# Seeeduino_XIAO_Expansion_board_v1_0_2008.net
KiCad netlist of a schematic drawn in EAGLE
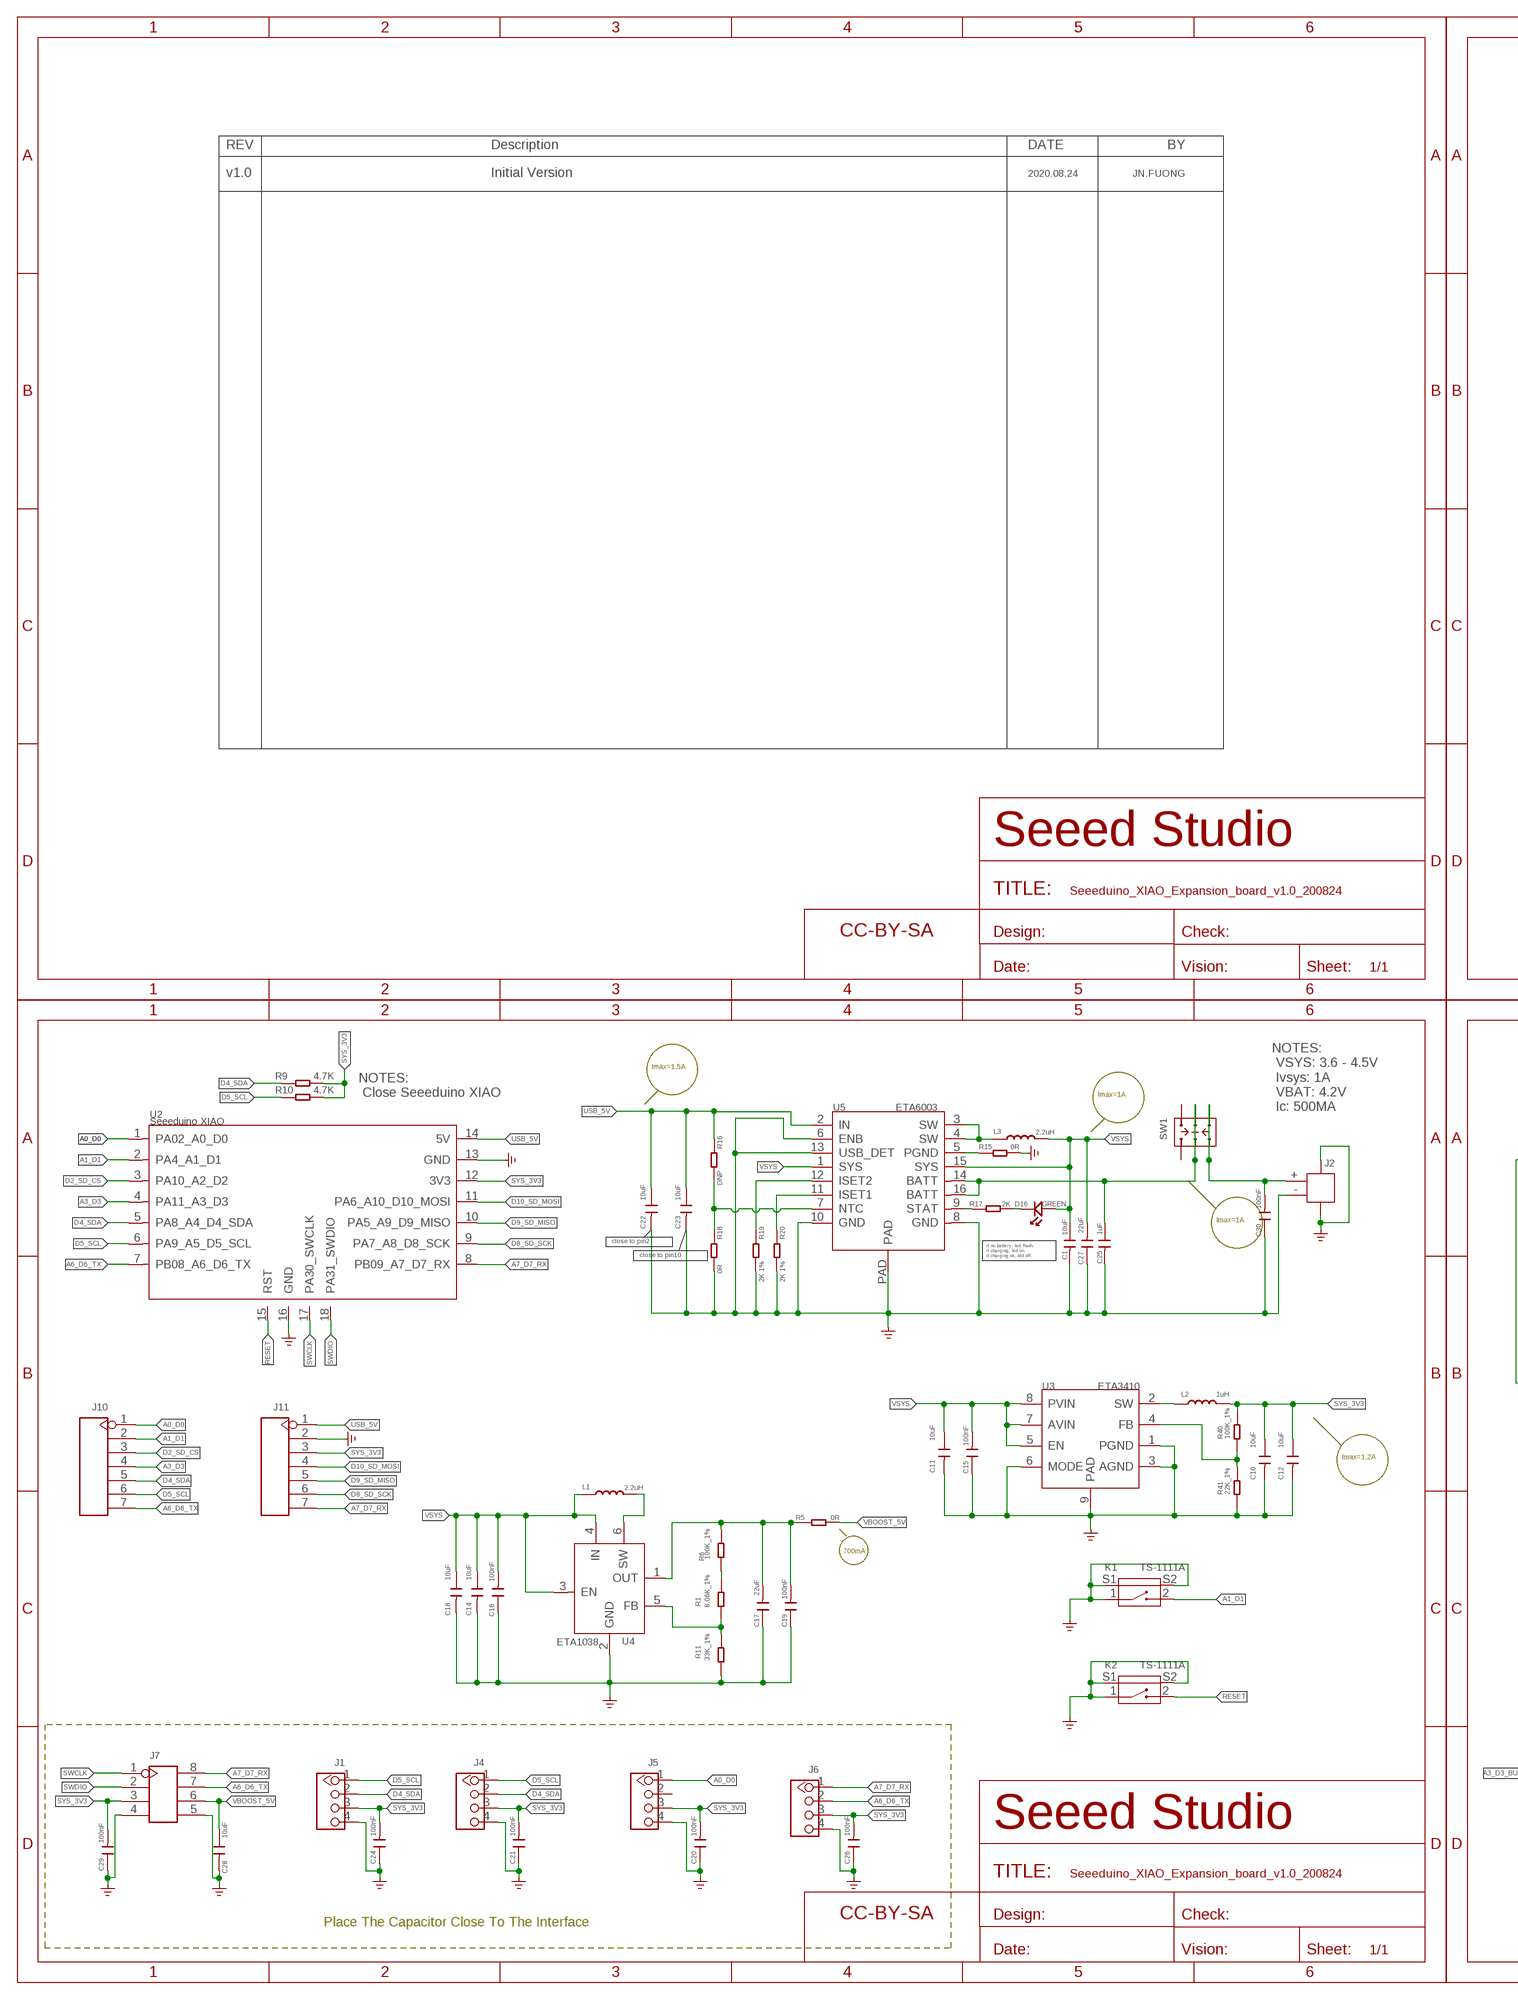
[diagram p0: schematic, sheet 1, part 1 of 2]
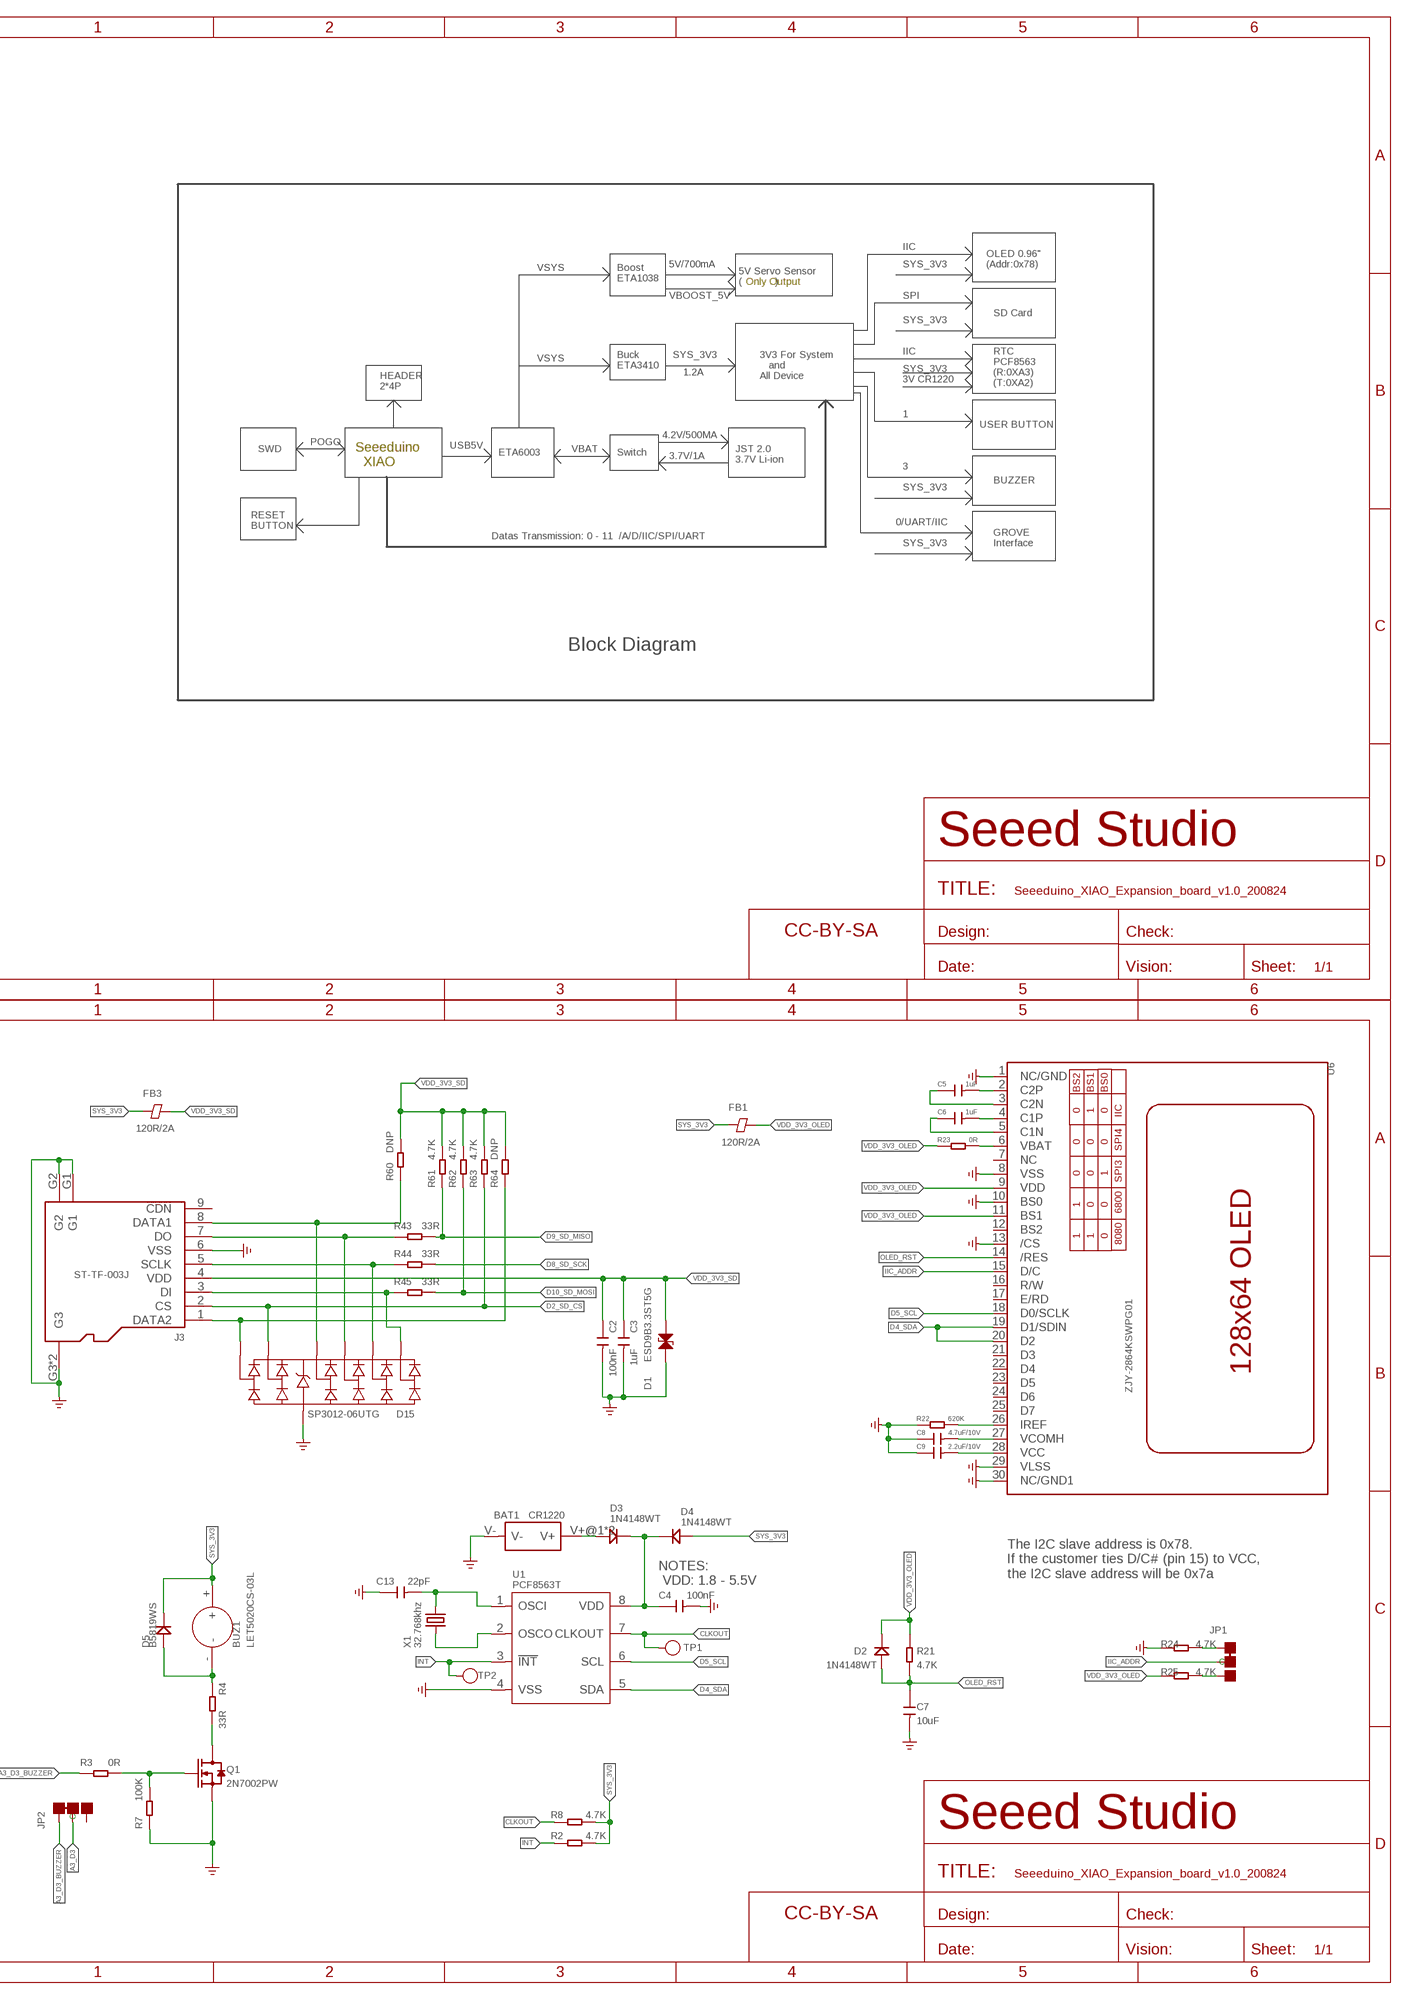
[diagram p1: schematic, sheet 1, part 2 of 2]

(export (version "E")
  (design (tool "Eeschema 10.0.6"))
  (components
    (comp (ref "BAT1")
      (value "CR1220")
      (footprint "eagle-import:BAT2P-SMD-13.2X12.1X3.2MM")
      (libsource (lib "eagle-import") (part "BAT-HOLDER-KST-1206"))
    )
    (comp (ref "BUZ1")
      (value "LET5020CS-03L")
      (footprint "eagle-import:BZ3-SMD-5.0X5.0X2.5MM")
      (libsource (lib "eagle-import") (part "BUZZER-312020004"))
    )
    (comp (ref "C1")
      (value "10uF")
      (footprint "eagle-import:C0603")
      (libsource (lib "eagle-import") (part "C-0603"))
    )
    (comp (ref "C2")
      (value "100nF")
      (footprint "eagle-import:C0402")
      (libsource (lib "eagle-import") (part "C-0402"))
    )
    (comp (ref "C3")
      (value "1uF")
      (footprint "eagle-import:C0402")
      (libsource (lib "eagle-import") (part "C-0402"))
    )
    (comp (ref "C4")
      (value "100nF")
      (footprint "eagle-import:C0402")
      (libsource (lib "eagle-import") (part "C-0402"))
    )
    (comp (ref "C5")
      (value "1uF")
      (footprint "eagle-import:C0402")
      (libsource (lib "eagle-import") (part "C-0402"))
    )
    (comp (ref "C6")
      (value "1uF")
      (footprint "eagle-import:C0402")
      (libsource (lib "eagle-import") (part "C-0402"))
    )
    (comp (ref "C7")
      (value "10uF")
      (footprint "eagle-import:C0603")
      (libsource (lib "eagle-import") (part "C-0603"))
    )
    (comp (ref "C8")
      (value "4.7uF/10V")
      (footprint "eagle-import:C0603")
      (libsource (lib "eagle-import") (part "C-0603"))
    )
    (comp (ref "C9")
      (value "2.2uF/10V")
      (footprint "eagle-import:C0603")
      (libsource (lib "eagle-import") (part "C-0603"))
    )
    (comp (ref "C10")
      (value "10uF")
      (footprint "eagle-import:C0603")
      (libsource (lib "eagle-import") (part "C-0603"))
    )
    (comp (ref "C11")
      (value "10uF")
      (footprint "eagle-import:C0603")
      (libsource (lib "eagle-import") (part "C-0603"))
    )
    (comp (ref "C12")
      (value "10uF")
      (footprint "eagle-import:C0603")
      (libsource (lib "eagle-import") (part "C-0603"))
    )
    (comp (ref "C13")
      (value "22pF")
      (footprint "eagle-import:C0402")
      (libsource (lib "eagle-import") (part "C-0402"))
    )
    (comp (ref "C14")
      (value "10uF")
      (footprint "eagle-import:C0603")
      (libsource (lib "eagle-import") (part "C-0603"))
    )
    (comp (ref "C15")
      (value "100nF")
      (footprint "eagle-import:C0402")
      (libsource (lib "eagle-import") (part "C-0402"))
    )
    (comp (ref "C16")
      (value "100nF")
      (footprint "eagle-import:C0402")
      (libsource (lib "eagle-import") (part "C-0402"))
    )
    (comp (ref "C17")
      (value "22uF")
      (footprint "eagle-import:C0603")
      (libsource (lib "eagle-import") (part "C-0603"))
    )
    (comp (ref "C18")
      (value "10uF")
      (footprint "eagle-import:C0603")
      (libsource (lib "eagle-import") (part "C-0603"))
    )
    (comp (ref "C19")
      (value "100nF")
      (footprint "eagle-import:C0402")
      (libsource (lib "eagle-import") (part "C-0402"))
    )
    (comp (ref "C20")
      (value "100nF")
      (footprint "eagle-import:C0402")
      (libsource (lib "eagle-import") (part "C-0402"))
    )
    (comp (ref "C21")
      (value "100nF")
      (footprint "eagle-import:C0402")
      (libsource (lib "eagle-import") (part "C-0402"))
    )
    (comp (ref "C22")
      (value "10uF")
      (footprint "eagle-import:C0603")
      (libsource (lib "eagle-import") (part "C-0603"))
    )
    (comp (ref "C23")
      (value "10uF")
      (footprint "eagle-import:C0603")
      (libsource (lib "eagle-import") (part "C-0603"))
    )
    (comp (ref "C24")
      (value "100nF")
      (footprint "eagle-import:C0402")
      (libsource (lib "eagle-import") (part "C-0402"))
    )
    (comp (ref "C25")
      (value "1uF")
      (footprint "eagle-import:C0402")
      (libsource (lib "eagle-import") (part "C-0402"))
    )
    (comp (ref "C26")
      (value "100nF")
      (footprint "eagle-import:C0402")
      (libsource (lib "eagle-import") (part "C-0402"))
    )
    (comp (ref "C27")
      (value "22uF")
      (footprint "eagle-import:C0603")
      (libsource (lib "eagle-import") (part "C-0603"))
    )
    (comp (ref "C28")
      (value "10uF")
      (footprint "eagle-import:C0603")
      (libsource (lib "eagle-import") (part "C-0603"))
    )
    (comp (ref "C29")
      (value "100nF")
      (footprint "eagle-import:C0402")
      (libsource (lib "eagle-import") (part "C-0402"))
    )
    (comp (ref "C30")
      (value "100nF")
      (footprint "eagle-import:C0603")
      (libsource (lib "eagle-import") (part "C-0603"))
    )
    (comp (ref "D1")
      (value "ESD9B3.3ST5G")
      (footprint "eagle-import:ESD-0402")
      (libsource (lib "eagle-import") (part "D-ESD-2P-DOUBLE-0402"))
    )
    (comp (ref "D2")
      (value "1N4148WT")
      (footprint "eagle-import:SOD-523")
      (libsource (lib "eagle-import") (part "DIODE'0603'"))
    )
    (comp (ref "D3")
      (value "1N4148WT")
      (footprint "eagle-import:SOD-523")
      (libsource (lib "eagle-import") (part "DIODE'0603'"))
    )
    (comp (ref "D4")
      (value "1N4148WT")
      (footprint "eagle-import:SOD-523")
      (libsource (lib "eagle-import") (part "DIODE'0603'"))
    )
    (comp (ref "D5")
      (value "B5819WS")
      (footprint "eagle-import:SOD-323")
      (libsource (lib "eagle-import") (part "DIODE'0805'"))
    )
    (comp (ref "D15")
      (value "SP3012-06UTG")
      (footprint "eagle-import:UDFN14-0.5-3.5X1.35X0.5MM")
      (libsource (lib "eagle-import") (part "D-ESD-14P"))
    )
    (comp (ref "D16")
      (value "GREEN")
      (footprint "eagle-import:LED-0402")
      (libsource (lib "eagle-import") (part "LED-0402"))
    )
    (comp (ref "FB1")
      (value "120R/2A")
      (footprint "eagle-import:F0402")
      (libsource (lib "eagle-import") (part "FERRITE-BEAD-0402"))
    )
    (comp (ref "FB3")
      (value "120R/2A")
      (footprint "eagle-import:F0402")
      (libsource (lib "eagle-import") (part "FERRITE-BEAD-0402"))
    )
    (comp (ref "FR1")
      (value "SEEEDSTUDIO-OPEN-SCH-FRAME")
      (footprint "eagle-import:SEEEDSTUDIO-PCB-FRAME")
      (libsource (lib "eagle-import") (part "SEEEDSTUDIO-OPEN-SCH-FRAME"))
    )
    (comp (ref "FR2")
      (value "SEEEDSTUDIO-OPEN-SCH-FRAME")
      (footprint "eagle-import:SEEEDSTUDIO-PCB-FRAME")
      (libsource (lib "eagle-import") (part "SEEEDSTUDIO-OPEN-SCH-FRAME"))
    )
    (comp (ref "FR3")
      (value "SEEEDSTUDIO-OPEN-SCH-FRAME")
      (footprint "eagle-import:SEEEDSTUDIO-PCB-FRAME")
      (libsource (lib "eagle-import") (part "SEEEDSTUDIO-OPEN-SCH-FRAME"))
    )
    (comp (ref "FR5")
      (value "SEEEDSTUDIO-OPEN-SCH-FRAME")
      (footprint "eagle-import:SEEEDSTUDIO-PCB-FRAME")
      (libsource (lib "eagle-import") (part "SEEEDSTUDIO-OPEN-SCH-FRAME"))
    )
    (comp (ref "J1")
      (value "GROVE-CONNECTOR-DIP-320110034")
      (footprint "eagle-import:HW4-2.0-90D")
      (libsource (lib "eagle-import") (part "GROVE-CONNECTOR-DIP-320110034"))
    )
    (comp (ref "J2")
      (value "JST-2P-SMD'2.0'")
      (footprint "eagle-import:HW2-SMD-2.0-90D")
      (libsource (lib "eagle-import") (part "JST-2P-SMD'2.0'"))
    )
    (comp (ref "J3")
      (value "ST-TF-003J")
      (footprint "eagle-import:MICRO-SD9+4P-SMD-16.1X14.5X1.85MM")
      (libsource (lib "eagle-import") (part "MICRO-SD-CARD-HOLDER-9P-320090000"))
    )
    (comp (ref "J4")
      (value "GROVE-CONNECTOR-DIP-320110034")
      (footprint "eagle-import:HW4-2.0-90D")
      (libsource (lib "eagle-import") (part "GROVE-CONNECTOR-DIP-320110034"))
    )
    (comp (ref "J5")
      (value "GROVE-CONNECTOR-DIP-320110034")
      (footprint "eagle-import:HW4-2.0-90D")
      (libsource (lib "eagle-import") (part "GROVE-CONNECTOR-DIP-320110034"))
    )
    (comp (ref "J6")
      (value "GROVE-CONNECTOR-DIP-320110034")
      (footprint "eagle-import:HW4-2.0-90D")
      (libsource (lib "eagle-import") (part "GROVE-CONNECTOR-DIP-320110034"))
    )
    (comp (ref "J7")
      (value "HEADER-2X4P-2.54-SMD")
      (footprint "eagle-import:H2X4-SMD-2.54")
      (libsource (lib "eagle-import") (part "HEADER-2X4P-2.54-SMD"))
    )
    (comp (ref "J10")
      (value "HEADER-7P-2.54")
      (footprint "eagle-import:H7-2.54")
      (libsource (lib "eagle-import") (part "HEADER-7P-2.54"))
    )
    (comp (ref "J11")
      (value "HEADER-7P-2.54")
      (footprint "eagle-import:H7-2.54")
      (libsource (lib "eagle-import") (part "HEADER-7P-2.54"))
    )
    (comp (ref "JP1")
      (value "JP-3P-SHORT")
      (footprint "eagle-import:3P-SMD-SHORT")
      (libsource (lib "eagle-import") (part "JP-3P-SHORT"))
    )
    (comp (ref "JP2")
      (value "JP-3P-SHORT")
      (footprint "eagle-import:3P-SMD-SHORT")
      (libsource (lib "eagle-import") (part "JP-3P-SHORT"))
    )
    (comp (ref "K1")
      (value "TS-1111A")
      (footprint "eagle-import:SW4-SMD-4.5X3.8X1.8MM-90D")
      (libsource (lib "eagle-import") (part "BUTTON-2+2P'HQ-TP-1100A'"))
    )
    (comp (ref "K2")
      (value "TS-1111A")
      (footprint "eagle-import:SW4-SMD-4.5X3.8X1.8MM-90D")
      (libsource (lib "eagle-import") (part "BUTTON-2+2P'HQ-TP-1100A'"))
    )
    (comp (ref "L1")
      (value "2.2uH")
      (footprint "eagle-import:L0806")
      (libsource (lib "eagle-import") (part "INDUCTOR/FERRITE-BEAD'0806'"))
    )
    (comp (ref "L2")
      (value "1uH")
      (footprint "eagle-import:L201610")
      (libsource (lib "eagle-import") (part "L-MPM201610SR33_T"))
    )
    (comp (ref "L3")
      (value "2.2uH")
      (footprint "eagle-import:L0806")
      (libsource (lib "eagle-import") (part "INDUCTOR/FERRITE-BEAD'0806'"))
    )
    (comp (ref "Q1")
      (value "2N7002PW")
      (footprint "eagle-import:SOT-323")
      (libsource (lib "eagle-import") (part "MOSFET-N-SI1304BDL"))
    )
    (comp (ref "R1")
      (value "8.06K_1%")
      (footprint "eagle-import:R0402")
      (libsource (lib "eagle-import") (part "R-0402"))
    )
    (comp (ref "R2")
      (value "4.7K")
      (footprint "eagle-import:R0402")
      (libsource (lib "eagle-import") (part "R-0402"))
    )
    (comp (ref "R3")
      (value "0R")
      (footprint "eagle-import:R0402")
      (libsource (lib "eagle-import") (part "R-0402"))
    )
    (comp (ref "R4")
      (value "33R")
      (footprint "eagle-import:R0402")
      (libsource (lib "eagle-import") (part "R-0402"))
    )
    (comp (ref "R5")
      (value "0R")
      (footprint "eagle-import:R0603")
      (libsource (lib "eagle-import") (part "R-0603"))
    )
    (comp (ref "R6")
      (value "100K_1%")
      (footprint "eagle-import:R0402")
      (libsource (lib "eagle-import") (part "R-0402"))
    )
    (comp (ref "R7")
      (value "100K")
      (footprint "eagle-import:R0402")
      (libsource (lib "eagle-import") (part "R-0402"))
    )
    (comp (ref "R8")
      (value "4.7K")
      (footprint "eagle-import:R0402")
      (libsource (lib "eagle-import") (part "R-0402"))
    )
    (comp (ref "R9")
      (value "4.7K")
      (footprint "eagle-import:R0402")
      (libsource (lib "eagle-import") (part "R-0402"))
    )
    (comp (ref "R10")
      (value "4.7K")
      (footprint "eagle-import:R0402")
      (libsource (lib "eagle-import") (part "R-0402"))
    )
    (comp (ref "R11")
      (value "33K_1%")
      (footprint "eagle-import:R0402")
      (libsource (lib "eagle-import") (part "R-0402"))
    )
    (comp (ref "R15")
      (value "0R")
      (footprint "eagle-import:R0402")
      (libsource (lib "eagle-import") (part "R-0402"))
    )
    (comp (ref "R16")
      (value "DNP")
      (footprint "eagle-import:R0402")
      (libsource (lib "eagle-import") (part "R-0402"))
    )
    (comp (ref "R17")
      (value "2K")
      (footprint "eagle-import:R0402")
      (libsource (lib "eagle-import") (part "R-0402"))
    )
    (comp (ref "R18")
      (value "0R")
      (footprint "eagle-import:R0402")
      (libsource (lib "eagle-import") (part "R-0402"))
    )
    (comp (ref "R19")
      (value "2K 1%")
      (footprint "eagle-import:R0402")
      (libsource (lib "eagle-import") (part "R-0402"))
    )
    (comp (ref "R20")
      (value "2K 1%")
      (footprint "eagle-import:R0402")
      (libsource (lib "eagle-import") (part "R-0402"))
    )
    (comp (ref "R21")
      (value "4.7K")
      (footprint "eagle-import:R0402")
      (libsource (lib "eagle-import") (part "R-0402"))
    )
    (comp (ref "R22")
      (value "620K")
      (footprint "eagle-import:R0402")
      (libsource (lib "eagle-import") (part "R-0402"))
    )
    (comp (ref "R23")
      (value "0R")
      (footprint "eagle-import:R0402")
      (libsource (lib "eagle-import") (part "R-0402"))
    )
    (comp (ref "R24")
      (value "4.7K")
      (footprint "eagle-import:R0402")
      (libsource (lib "eagle-import") (part "R-0402"))
    )
    (comp (ref "R25")
      (value "4.7K")
      (footprint "eagle-import:R0402")
      (libsource (lib "eagle-import") (part "R-0402"))
    )
    (comp (ref "R40")
      (value "100K_1%")
      (footprint "eagle-import:R0402")
      (libsource (lib "eagle-import") (part "R-0402"))
    )
    (comp (ref "R41")
      (value "22K_1%")
      (footprint "eagle-import:R0402")
      (libsource (lib "eagle-import") (part "R-0402"))
    )
    (comp (ref "R43")
      (value "33R")
      (footprint "eagle-import:R0402")
      (libsource (lib "eagle-import") (part "R-0402"))
    )
    (comp (ref "R44")
      (value "33R")
      (footprint "eagle-import:R0402")
      (libsource (lib "eagle-import") (part "R-0402"))
    )
    (comp (ref "R45")
      (value "33R")
      (footprint "eagle-import:R0402")
      (libsource (lib "eagle-import") (part "R-0402"))
    )
    (comp (ref "R60")
      (value "DNP")
      (footprint "eagle-import:R0402")
      (libsource (lib "eagle-import") (part "R-0402"))
    )
    (comp (ref "R61")
      (value "4.7K")
      (footprint "eagle-import:R0402")
      (libsource (lib "eagle-import") (part "R-0402"))
    )
    (comp (ref "R62")
      (value "4.7K")
      (footprint "eagle-import:R0402")
      (libsource (lib "eagle-import") (part "R-0402"))
    )
    (comp (ref "R63")
      (value "4.7K")
      (footprint "eagle-import:R0402")
      (libsource (lib "eagle-import") (part "R-0402"))
    )
    (comp (ref "R64")
      (value "DNP")
      (footprint "eagle-import:R0402")
      (libsource (lib "eagle-import") (part "R-0402"))
    )
    (comp (ref "SW1")
      (value "SWITCH-2CH-6P-311030004")
      (footprint "eagle-import:SW6-2.54-9.0X3.5X3.2MM-90D")
      (libsource (lib "eagle-import") (part "SWITCH-2CH-6P-311030004"))
    )
    (comp (ref "TP1")
      (value "TEST-POINT'4545'")
      (footprint "eagle-import:TP-D45MIL")
      (fields (field (name "PARTNO") "DNP"))
      (libsource (lib "eagle-import") (part "TEST-POINT'4545'"))
    )
    (comp (ref "TP2")
      (value "TEST-POINT'4545'")
      (footprint "eagle-import:TP-D45MIL")
      (fields (field (name "PARTNO") "DNP"))
      (libsource (lib "eagle-import") (part "TEST-POINT'4545'"))
    )
    (comp (ref "U1")
      (value "PCF8563T")
      (footprint "eagle-import:SOP8-1.27-5X3.9MM")
      (libsource (lib "eagle-import") (part "RTC-PCF8563T"))
    )
    (comp (ref "U2")
      (value "Seeeduino XIAO")
      (footprint "eagle-import:MOUDLE14P-2.54-21X17.8MM-TEST")
      (libsource (lib "eagle-import") (part "MOUDLE-SEEEDUINO-XIAO-TEST-DIP"))
    )
    (comp (ref "U3")
      (value "ETA3410")
      (footprint "eagle-import:DFN8G-0.5-2X2MM")
      (libsource (lib "eagle-import") (part "CONVERTER-ETA3410"))
    )
    (comp (ref "U4")
      (value "ETA1038")
      (footprint "eagle-import:SOT-23-6")
      (libsource (lib "eagle-import") (part "CONVERTER-ETA1038"))
    )
    (comp (ref "U5")
      (value "ETA6003")
      (footprint "eagle-import:QFN16GA-0.5-3X3MM")
      (libsource (lib "eagle-import") (part "PMIC-ETA6003-310990023"))
    )
    (comp (ref "U6")
      (value "ZJY-2864KSWPG01")
      (footprint "eagle-import:OLED30P-0.7-24.74X16.9MM")
      (libsource (lib "eagle-import") (part "OLED-12864-30P"))
    )
    (comp (ref "X1")
      (value "32.768khz")
      (footprint "eagle-import:X2-SMD-L2.0X1.2X0.55MM")
      (libsource (lib "eagle-import") (part "CRYSTAL-2P'NX2012SA'"))
    )
  )
  (nets
    (net (code "1") (name "A0_D0") (class "Default")
      (node (ref "J10") (pin "1") (pinfunction "1_1") (pintype "bidirectional"))
      (node (ref "J5") (pin "1") (pinfunction "1_1") (pintype "bidirectional"))
      (node (ref "U2") (pin "1") (pinfunction "PA02_A0_D0_1") (pintype "bidirectional"))
    )
    (net (code "2") (name "A1_D1") (class "Default")
      (node (ref "J10") (pin "2") (pinfunction "2_2") (pintype "bidirectional"))
      (node (ref "K1") (pin "2") (pinfunction "2_2") (pintype "bidirectional"))
      (node (ref "U2") (pin "2") (pinfunction "PA4_A1_D1_2") (pintype "bidirectional"))
    )
    (net (code "3") (name "A3_D3") (class "Default")
      (node (ref "J10") (pin "4") (pinfunction "4_4") (pintype "bidirectional"))
      (node (ref "JP2") (pin "MM") (pinfunction "C_MM") (pintype "bidirectional"))
      (node (ref "U2") (pin "4") (pinfunction "PA11_A3_D3_4") (pintype "bidirectional"))
    )
    (net (code "4") (name "A3_D3_BUZZER") (class "Default")
      (node (ref "JP2") (pin "11") (pinfunction "L_11") (pintype "bidirectional"))
      (node (ref "R3") (pin "1") (pinfunction "1_1") (pintype "passive"))
    )
    (net (code "5") (name "A6_D6_TX") (class "Default")
      (node (ref "J10") (pin "7") (pinfunction "7_7") (pintype "bidirectional"))
      (node (ref "J6") (pin "2") (pinfunction "2_2") (pintype "bidirectional"))
      (node (ref "J7") (pin "7") (pinfunction "7_7") (pintype "bidirectional"))
      (node (ref "U2") (pin "7") (pinfunction "PB08_A6_D6_TX_7") (pintype "bidirectional"))
    )
    (net (code "6") (name "A7_D7_RX") (class "Default")
      (node (ref "J11") (pin "7") (pinfunction "7_7") (pintype "bidirectional"))
      (node (ref "J6") (pin "1") (pinfunction "1_1") (pintype "bidirectional"))
      (node (ref "J7") (pin "8") (pinfunction "8_8") (pintype "bidirectional"))
      (node (ref "U2") (pin "8") (pinfunction "PB09_A7_D7_RX_8") (pintype "bidirectional"))
    )
    (net (code "7") (name "CLKOUT") (class "Default")
      (node (ref "R8") (pin "1") (pinfunction "1_1") (pintype "passive"))
      (node (ref "TP1") (pin "T") (pinfunction "T_T") (pintype "bidirectional"))
      (node (ref "U1") (pin "7") (pinfunction "CLKOUT_7") (pintype "bidirectional"))
    )
    (net (code "8") (name "D2_SD_CS") (class "Default")
      (node (ref "D15") (pin "6") (pinfunction "9_6") (pintype "bidirectional"))
      (node (ref "D15") (pin "9") (pinfunction "9_9") (pintype "bidirectional"))
      (node (ref "J10") (pin "3") (pinfunction "3_3") (pintype "bidirectional"))
      (node (ref "J3") (pin "2") (pinfunction "CS_2") (pintype "bidirectional"))
      (node (ref "R63") (pin "1") (pinfunction "1_1") (pintype "passive"))
      (node (ref "U2") (pin "3") (pinfunction "PA10_A2_D2_3") (pintype "bidirectional"))
    )
    (net (code "9") (name "D4_SDA") (class "Default")
      (node (ref "J1") (pin "2") (pinfunction "2_2") (pintype "bidirectional"))
      (node (ref "J10") (pin "5") (pinfunction "5_5") (pintype "bidirectional"))
      (node (ref "J4") (pin "2") (pinfunction "2_2") (pintype "bidirectional"))
      (node (ref "R9") (pin "1") (pinfunction "1_1") (pintype "passive"))
      (node (ref "U1") (pin "5") (pinfunction "SDA_5") (pintype "bidirectional"))
      (node (ref "U2") (pin "5") (pinfunction "PA8_A4_D4_SDA_5") (pintype "bidirectional"))
      (node (ref "U6") (pin "19") (pinfunction "D1/SDIN_19") (pintype "bidirectional"))
      (node (ref "U6") (pin "20") (pinfunction "D2_20") (pintype "input"))
    )
    (net (code "10") (name "D5_SCL") (class "Default")
      (node (ref "J1") (pin "1") (pinfunction "1_1") (pintype "bidirectional"))
      (node (ref "J10") (pin "6") (pinfunction "6_6") (pintype "bidirectional"))
      (node (ref "J4") (pin "1") (pinfunction "1_1") (pintype "bidirectional"))
      (node (ref "R10") (pin "1") (pinfunction "1_1") (pintype "passive"))
      (node (ref "U1") (pin "6") (pinfunction "SCL_6") (pintype "bidirectional"))
      (node (ref "U2") (pin "6") (pinfunction "PA9_A5_D5_SCL_6") (pintype "bidirectional"))
      (node (ref "U6") (pin "18") (pinfunction "D0/SCLK_18") (pintype "bidirectional"))
    )
    (net (code "11") (name "D8_SD_SCK") (class "Default")
      (node (ref "J11") (pin "6") (pinfunction "6_6") (pintype "bidirectional"))
      (node (ref "R44") (pin "2") (pinfunction "2_2") (pintype "passive"))
      (node (ref "U2") (pin "9") (pinfunction "PA7_A8_D8_SCK_9") (pintype "bidirectional"))
    )
    (net (code "12") (name "D9_SD_MISO") (class "Default")
      (node (ref "J11") (pin "5") (pinfunction "5_5") (pintype "bidirectional"))
      (node (ref "R43") (pin "2") (pinfunction "2_2") (pintype "passive"))
      (node (ref "R61") (pin "1") (pinfunction "1_1") (pintype "passive"))
      (node (ref "U2") (pin "10") (pinfunction "PA5_A9_D9_MISO_10") (pintype "bidirectional"))
    )
    (net (code "13") (name "D10_SD_MOSI") (class "Default")
      (node (ref "J11") (pin "4") (pinfunction "4_4") (pintype "bidirectional"))
      (node (ref "R45") (pin "2") (pinfunction "2_2") (pintype "passive"))
      (node (ref "R62") (pin "1") (pinfunction "1_1") (pintype "passive"))
      (node (ref "U2") (pin "11") (pinfunction "PA6_A10_D10_MOSI_11") (pintype "bidirectional"))
    )
    (net (code "14") (name "GND_POWER") (class "Default")
      (node (ref "BAT1") (pin "V-") (pinfunction "V-_V-") (pintype "bidirectional"))
      (node (ref "C1") (pin "2") (pinfunction "2_2") (pintype "passive"))
      (node (ref "C10") (pin "2") (pinfunction "2_2") (pintype "passive"))
      (node (ref "C11") (pin "2") (pinfunction "2_2") (pintype "passive"))
      (node (ref "C12") (pin "2") (pinfunction "2_2") (pintype "passive"))
      (node (ref "C13") (pin "1") (pinfunction "1_1") (pintype "passive"))
      (node (ref "C14") (pin "2") (pinfunction "2_2") (pintype "passive"))
      (node (ref "C15") (pin "1") (pinfunction "1_1") (pintype "passive"))
      (node (ref "C16") (pin "1") (pinfunction "1_1") (pintype "passive"))
      (node (ref "C17") (pin "1") (pinfunction "1_1") (pintype "passive"))
      (node (ref "C18") (pin "2") (pinfunction "2_2") (pintype "passive"))
      (node (ref "C19") (pin "1") (pinfunction "1_1") (pintype "passive"))
      (node (ref "C2") (pin "2") (pinfunction "2_2") (pintype "passive"))
      (node (ref "C20") (pin "1") (pinfunction "1_1") (pintype "passive"))
      (node (ref "C21") (pin "1") (pinfunction "1_1") (pintype "passive"))
      (node (ref "C22") (pin "2") (pinfunction "2_2") (pintype "passive"))
      (node (ref "C23") (pin "2") (pinfunction "2_2") (pintype "passive"))
      (node (ref "C24") (pin "1") (pinfunction "1_1") (pintype "passive"))
      (node (ref "C25") (pin "2") (pinfunction "2_2") (pintype "passive"))
      (node (ref "C26") (pin "1") (pinfunction "1_1") (pintype "passive"))
      (node (ref "C27") (pin "1") (pinfunction "1_1") (pintype "passive"))
      (node (ref "C28") (pin "2") (pinfunction "2_2") (pintype "passive"))
      (node (ref "C29") (pin "1") (pinfunction "1_1") (pintype "passive"))
      (node (ref "C3") (pin "2") (pinfunction "2_2") (pintype "passive"))
      (node (ref "C30") (pin "1") (pinfunction "1_1") (pintype "passive"))
      (node (ref "C4") (pin "2") (pinfunction "2_2") (pintype "passive"))
      (node (ref "C7") (pin "2") (pinfunction "2_2") (pintype "passive"))
      (node (ref "C8") (pin "1") (pinfunction "1_1") (pintype "passive"))
      (node (ref "C9") (pin "1") (pinfunction "1_1") (pintype "passive"))
      (node (ref "D1") (pin "1") (pinfunction "1_1") (pintype "bidirectional"))
      (node (ref "D15") (pin "10") (pinfunction "10_10") (pintype "bidirectional"))
      (node (ref "D15") (pin "5") (pinfunction "10_5") (pintype "bidirectional"))
      (node (ref "J1") (pin "4") (pinfunction "4_4") (pintype "bidirectional"))
      (node (ref "J11") (pin "2") (pinfunction "2_2") (pintype "bidirectional"))
      (node (ref "J2") (pin "-") (pinfunction "2_-") (pintype "bidirectional"))
      (node (ref "J2") (pin "3") (pinfunction "3_3") (pintype "bidirectional"))
      (node (ref "J2") (pin "4") (pinfunction "4_4") (pintype "bidirectional"))
      (node (ref "J3") (pin "6") (pinfunction "VSS_6") (pintype "bidirectional"))
      (node (ref "J3") (pin "G1") (pinfunction "G1_G1") (pintype "bidirectional"))
      (node (ref "J3") (pin "G2") (pinfunction "G2_G2") (pintype "bidirectional"))
      (node (ref "J3") (pin "G3") (pinfunction "G3_G3") (pintype "bidirectional"))
      (node (ref "J3") (pin "G4") (pinfunction "G3_G4") (pintype "bidirectional"))
      (node (ref "J4") (pin "4") (pinfunction "4_4") (pintype "bidirectional"))
      (node (ref "J5") (pin "4") (pinfunction "4_4") (pintype "bidirectional"))
      (node (ref "J6") (pin "4") (pinfunction "4_4") (pintype "bidirectional"))
      (node (ref "J7") (pin "4") (pinfunction "4_4") (pintype "bidirectional"))
      (node (ref "J7") (pin "5") (pinfunction "5_5") (pintype "bidirectional"))
      (node (ref "K1") (pin "1") (pinfunction "1_1") (pintype "bidirectional"))
      (node (ref "K1") (pin "S1") (pinfunction "S1_S1") (pintype "bidirectional"))
      (node (ref "K1") (pin "S2") (pinfunction "S2_S2") (pintype "bidirectional"))
      (node (ref "K2") (pin "1") (pinfunction "1_1") (pintype "bidirectional"))
      (node (ref "K2") (pin "S1") (pinfunction "S1_S1") (pintype "bidirectional"))
      (node (ref "K2") (pin "S2") (pinfunction "S2_S2") (pintype "bidirectional"))
      (node (ref "Q1") (pin "2") (pinfunction "S_2") (pintype "passive"))
      (node (ref "R11") (pin "2") (pinfunction "2_2") (pintype "passive"))
      (node (ref "R15") (pin "2") (pinfunction "2_2") (pintype "passive"))
      (node (ref "R18") (pin "2") (pinfunction "2_2") (pintype "passive"))
      (node (ref "R19") (pin "2") (pinfunction "2_2") (pintype "passive"))
      (node (ref "R20") (pin "2") (pinfunction "2_2") (pintype "passive"))
      (node (ref "R22") (pin "2") (pinfunction "2_2") (pintype "passive"))
      (node (ref "R24") (pin "1") (pinfunction "1_1") (pintype "passive"))
      (node (ref "R41") (pin "1") (pinfunction "1_1") (pintype "passive"))
      (node (ref "R7") (pin "1") (pinfunction "1_1") (pintype "passive"))
      (node (ref "U1") (pin "4") (pinfunction "VSS_4") (pintype "bidirectional"))
      (node (ref "U2") (pin "13") (pinfunction "GND_13") (pintype "bidirectional"))
      (node (ref "U2") (pin "16") (pinfunction "GND_16") (pintype "bidirectional"))
      (node (ref "U3") (pin "1") (pinfunction "PGND_1") (pintype "bidirectional"))
      (node (ref "U3") (pin "3") (pinfunction "AGND_3") (pintype "bidirectional"))
      (node (ref "U3") (pin "6") (pinfunction "MODE_6") (pintype "bidirectional"))
      (node (ref "U3") (pin "9") (pinfunction "PAD_9") (pintype "bidirectional"))
      (node (ref "U4") (pin "2") (pinfunction "GND_2") (pintype "bidirectional"))
      (node (ref "U5") (pin "10") (pinfunction "GND_10") (pintype "bidirectional"))
      (node (ref "U5") (pin "13") (pinfunction "USB_DET_13") (pintype "bidirectional"))
      (node (ref "U5") (pin "6") (pinfunction "ENB_6") (pintype "bidirectional"))
      (node (ref "U5") (pin "8") (pinfunction "GND_8") (pintype "bidirectional"))
      (node (ref "U5") (pin "PAD") (pinfunction "PAD_PAD") (pintype "bidirectional"))
      (node (ref "U6") (pin "1") (pinfunction "NC/GND_1") (pintype "input"))
      (node (ref "U6") (pin "10") (pinfunction "BS0_10") (pintype "input"))
      (node (ref "U6") (pin "13") (pinfunction "/CS_13") (pintype "input"))
      (node (ref "U6") (pin "29") (pinfunction "VLSS_29") (pintype "power_in"))
      (node (ref "U6") (pin "30") (pinfunction "NC/GND1_30") (pintype "input"))
      (node (ref "U6") (pin "8") (pinfunction "VSS_8") (pintype "power_in"))
    )
    (net (code "15") (name "IIC_ADDR") (class "Default")
      (node (ref "JP1") (pin "MM") (pinfunction "C_MM") (pintype "bidirectional"))
      (node (ref "U6") (pin "15") (pinfunction "D/C_15") (pintype "input"))
    )
    (net (code "16") (name "INT") (class "Default")
      (node (ref "R2") (pin "1") (pinfunction "1_1") (pintype "passive"))
      (node (ref "TP2") (pin "T") (pinfunction "T_T") (pintype "bidirectional"))
      (node (ref "U1") (pin "3") (pinfunction "~{INT}_3") (pintype "bidirectional"))
    )
    (net (code "17") (name "Net-(BAT1-V+-PadV+@1)") (class "Default")
      (node (ref "BAT1") (pin "V+@1") (pinfunction "V+_V+@1") (pintype "bidirectional"))
      (node (ref "BAT1") (pin "V+@2") (pinfunction "V+_V+@2") (pintype "bidirectional"))
      (node (ref "D3") (pin "+") (pinfunction "+_+") (pintype "passive"))
    )
    (net (code "18") (name "Net-(BUZ1-Pad-)") (class "Default")
      (node (ref "BUZ1") (pin "-") (pinfunction "-_-") (pintype "bidirectional"))
      (node (ref "D5") (pin "+") (pinfunction "+_+") (pintype "passive"))
      (node (ref "R4") (pin "1") (pinfunction "1_1") (pintype "passive"))
    )
    (net (code "19") (name "Net-(C25-Pad1)") (class "Default")
      (node (ref "C25") (pin "1") (pinfunction "1_1") (pintype "passive"))
      (node (ref "SW1") (pin "COM1") (pinfunction "COM1_COM1") (pintype "bidirectional"))
      (node (ref "SW1") (pin "COM2") (pinfunction "COM2_COM2") (pintype "bidirectional"))
      (node (ref "U5") (pin "14") (pinfunction "BATT_14") (pintype "bidirectional"))
      (node (ref "U5") (pin "16") (pinfunction "BATT_16") (pintype "bidirectional"))
    )
    (net (code "20") (name "Net-(D16-Pad-)") (class "Default")
      (node (ref "D16") (pin "-") (pinfunction "-_-") (pintype "passive"))
      (node (ref "R17") (pin "1") (pinfunction "1_1") (pintype "passive"))
    )
    (net (code "21") (name "Net-(J2-1)") (class "Default")
      (node (ref "C30") (pin "2") (pinfunction "2_2") (pintype "passive"))
      (node (ref "J2") (pin "+") (pinfunction "1_+") (pintype "bidirectional"))
      (node (ref "SW1") (pin "CH1B") (pinfunction "CH1B_CH1B") (pintype "bidirectional"))
      (node (ref "SW1") (pin "CH2B") (pinfunction "CH2B_CH2B") (pintype "bidirectional"))
    )
    (net (code "22") (name "Net-(J3-DATA1)") (class "Default")
      (node (ref "D15") (pin "1") (pinfunction "14_1") (pintype "bidirectional"))
      (node (ref "D15") (pin "14") (pinfunction "14_14") (pintype "bidirectional"))
      (node (ref "J3") (pin "8") (pinfunction "DATA1_8") (pintype "bidirectional"))
      (node (ref "R60") (pin "1") (pinfunction "1_1") (pintype "passive"))
    )
    (net (code "23") (name "Net-(J3-DATA2)") (class "Default")
      (node (ref "D15") (pin "7") (pinfunction "8_7") (pintype "bidirectional"))
      (node (ref "D15") (pin "8") (pinfunction "8_8") (pintype "bidirectional"))
      (node (ref "J3") (pin "1") (pinfunction "DATA2_1") (pintype "bidirectional"))
      (node (ref "R64") (pin "1") (pinfunction "1_1") (pintype "passive"))
    )
    (net (code "24") (name "Net-(J3-DI)") (class "Default")
      (node (ref "D15") (pin "11") (pinfunction "11_11") (pintype "bidirectional"))
      (node (ref "D15") (pin "4") (pinfunction "11_4") (pintype "bidirectional"))
      (node (ref "J3") (pin "3") (pinfunction "DI_3") (pintype "bidirectional"))
      (node (ref "R45") (pin "1") (pinfunction "1_1") (pintype "passive"))
    )
    (net (code "25") (name "Net-(J3-DO)") (class "Default")
      (node (ref "D15") (pin "13") (pinfunction "13_13") (pintype "bidirectional"))
      (node (ref "D15") (pin "2") (pinfunction "13_2") (pintype "bidirectional"))
      (node (ref "J3") (pin "7") (pinfunction "DO_7") (pintype "bidirectional"))
      (node (ref "R43") (pin "1") (pinfunction "1_1") (pintype "passive"))
    )
    (net (code "26") (name "Net-(J3-SCLK)") (class "Default")
      (node (ref "D15") (pin "12") (pinfunction "12_12") (pintype "bidirectional"))
      (node (ref "D15") (pin "3") (pinfunction "12_3") (pintype "bidirectional"))
      (node (ref "J3") (pin "5") (pinfunction "SCLK_5") (pintype "bidirectional"))
      (node (ref "R44") (pin "1") (pinfunction "1_1") (pintype "passive"))
    )
    (net (code "27") (name "Net-(JP1-L)") (class "Default")
      (node (ref "JP1") (pin "11") (pinfunction "L_11") (pintype "bidirectional"))
      (node (ref "R24") (pin "2") (pinfunction "2_2") (pintype "passive"))
    )
    (net (code "28") (name "Net-(JP1-R)") (class "Default")
      (node (ref "JP1") (pin "00") (pinfunction "R_00") (pintype "bidirectional"))
      (node (ref "R25") (pin "2") (pinfunction "2_2") (pintype "passive"))
    )
    (net (code "29") (name "Net-(L3-Pad1)") (class "Default")
      (node (ref "L3") (pin "1") (pinfunction "1_1") (pintype "passive"))
      (node (ref "U5") (pin "3") (pinfunction "SW_3") (pintype "bidirectional"))
      (node (ref "U5") (pin "4") (pinfunction "SW_4") (pintype "bidirectional"))
    )
    (net (code "30") (name "Net-(Q1-D)") (class "Default")
      (node (ref "Q1") (pin "3") (pinfunction "D_3") (pintype "passive"))
      (node (ref "R4") (pin "2") (pinfunction "2_2") (pintype "passive"))
    )
    (net (code "31") (name "Net-(Q1-G)") (class "Default")
      (node (ref "Q1") (pin "1") (pinfunction "G_1") (pintype "passive"))
      (node (ref "R3") (pin "2") (pinfunction "2_2") (pintype "passive"))
      (node (ref "R7") (pin "2") (pinfunction "2_2") (pintype "passive"))
    )
    (net (code "32") (name "Net-(R1-Pad1)") (class "Default")
      (node (ref "R1") (pin "1") (pinfunction "1_1") (pintype "passive"))
      (node (ref "R6") (pin "2") (pinfunction "2_2") (pintype "passive"))
    )
    (net (code "33") (name "Net-(U1-OSCI)") (class "Default")
      (node (ref "C13") (pin "2") (pinfunction "2_2") (pintype "passive"))
      (node (ref "U1") (pin "1") (pinfunction "OSCI_1") (pintype "bidirectional"))
      (node (ref "X1") (pin "2") (pinfunction "2_2") (pintype "passive"))
    )
    (net (code "34") (name "Net-(U1-OSCO)") (class "Default")
      (node (ref "U1") (pin "2") (pinfunction "OSCO_2") (pintype "bidirectional"))
      (node (ref "X1") (pin "1") (pinfunction "1_1") (pintype "passive"))
    )
    (net (code "35") (name "Net-(U1-VDD)") (class "Default")
      (node (ref "C4") (pin "1") (pinfunction "1_1") (pintype "passive"))
      (node (ref "D3") (pin "-") (pinfunction "-_-") (pintype "passive"))
      (node (ref "D4") (pin "-") (pinfunction "-_-") (pintype "passive"))
      (node (ref "U1") (pin "8") (pinfunction "VDD_8") (pintype "bidirectional"))
    )
    (net (code "36") (name "Net-(U3-FB)") (class "Default")
      (node (ref "R40") (pin "1") (pinfunction "1_1") (pintype "passive"))
      (node (ref "R41") (pin "2") (pinfunction "2_2") (pintype "passive"))
      (node (ref "U3") (pin "4") (pinfunction "FB_4") (pintype "bidirectional"))
    )
    (net (code "37") (name "Net-(U3-SW)") (class "Default")
      (node (ref "L2") (pin "1") (pinfunction "1_1") (pintype "passive"))
      (node (ref "U3") (pin "2") (pinfunction "SW_2") (pintype "bidirectional"))
    )
    (net (code "38") (name "Net-(U4-FB)") (class "Default")
      (node (ref "R1") (pin "2") (pinfunction "2_2") (pintype "passive"))
      (node (ref "R11") (pin "1") (pinfunction "1_1") (pintype "passive"))
      (node (ref "U4") (pin "5") (pinfunction "FB_5") (pintype "bidirectional"))
    )
    (net (code "39") (name "Net-(U4-OUT)") (class "Default")
      (node (ref "C17") (pin "2") (pinfunction "2_2") (pintype "passive"))
      (node (ref "C19") (pin "2") (pinfunction "2_2") (pintype "passive"))
      (node (ref "R5") (pin "2") (pinfunction "2_2") (pintype "passive"))
      (node (ref "R6") (pin "1") (pinfunction "1_1") (pintype "passive"))
      (node (ref "U4") (pin "1") (pinfunction "OUT_1") (pintype "bidirectional"))
    )
    (net (code "40") (name "Net-(U4-SW)") (class "Default")
      (node (ref "L1") (pin "2") (pinfunction "2_2") (pintype "passive"))
      (node (ref "U4") (pin "6") (pinfunction "SW_6") (pintype "bidirectional"))
    )
    (net (code "41") (name "Net-(U5-ISET1)") (class "Default")
      (node (ref "R20") (pin "1") (pinfunction "1_1") (pintype "passive"))
      (node (ref "U5") (pin "11") (pinfunction "ISET1_11") (pintype "bidirectional"))
    )
    (net (code "42") (name "Net-(U5-ISET2)") (class "Default")
      (node (ref "R19") (pin "1") (pinfunction "1_1") (pintype "passive"))
      (node (ref "U5") (pin "12") (pinfunction "ISET2_12") (pintype "bidirectional"))
    )
    (net (code "43") (name "Net-(U5-NTC)") (class "Default")
      (node (ref "R16") (pin "2") (pinfunction "2_2") (pintype "passive"))
      (node (ref "R18") (pin "1") (pinfunction "1_1") (pintype "passive"))
      (node (ref "U5") (pin "7") (pinfunction "NTC_7") (pintype "bidirectional"))
    )
    (net (code "44") (name "Net-(U5-PGND)") (class "Default")
      (node (ref "R15") (pin "1") (pinfunction "1_1") (pintype "passive"))
      (node (ref "U5") (pin "5") (pinfunction "PGND_5") (pintype "bidirectional"))
    )
    (net (code "45") (name "Net-(U5-STAT)") (class "Default")
      (node (ref "R17") (pin "2") (pinfunction "2_2") (pintype "passive"))
      (node (ref "U5") (pin "9") (pinfunction "STAT_9") (pintype "bidirectional"))
    )
    (net (code "46") (name "Net-(U6-C1N)") (class "Default")
      (node (ref "C6") (pin "1") (pinfunction "1_1") (pintype "passive"))
      (node (ref "U6") (pin "5") (pinfunction "C1N_5") (pintype "input"))
    )
    (net (code "47") (name "Net-(U6-C1P)") (class "Default")
      (node (ref "C6") (pin "2") (pinfunction "2_2") (pintype "passive"))
      (node (ref "U6") (pin "4") (pinfunction "C1P_4") (pintype "input"))
    )
    (net (code "48") (name "Net-(U6-C2N)") (class "Default")
      (node (ref "C5") (pin "1") (pinfunction "1_1") (pintype "passive"))
      (node (ref "U6") (pin "3") (pinfunction "C2N_3") (pintype "input"))
    )
    (net (code "49") (name "Net-(U6-C2P)") (class "Default")
      (node (ref "C5") (pin "2") (pinfunction "2_2") (pintype "passive"))
      (node (ref "U6") (pin "2") (pinfunction "C2P_2") (pintype "input"))
    )
    (net (code "50") (name "Net-(U6-IREF)") (class "Default")
      (node (ref "R22") (pin "1") (pinfunction "1_1") (pintype "passive"))
      (node (ref "U6") (pin "26") (pinfunction "IREF_26") (pintype "input"))
    )
    (net (code "51") (name "Net-(U6-VBAT)") (class "Default")
      (node (ref "R23") (pin "2") (pinfunction "2_2") (pintype "passive"))
      (node (ref "U6") (pin "6") (pinfunction "VBAT_6") (pintype "input"))
    )
    (net (code "52") (name "Net-(U6-VCC)") (class "Default")
      (node (ref "C9") (pin "2") (pinfunction "2_2") (pintype "passive"))
      (node (ref "U6") (pin "28") (pinfunction "VCC_28") (pintype "power_in"))
    )
    (net (code "53") (name "Net-(U6-VCOMH)") (class "Default")
      (node (ref "C8") (pin "2") (pinfunction "2_2") (pintype "passive"))
      (node (ref "U6") (pin "27") (pinfunction "VCOMH_27") (pintype "output"))
    )
    (net (code "54") (name "OLED_RST") (class "Default")
      (node (ref "C7") (pin "1") (pinfunction "1_1") (pintype "passive"))
      (node (ref "D2") (pin "+") (pinfunction "+_+") (pintype "passive"))
      (node (ref "R21") (pin "1") (pinfunction "1_1") (pintype "passive"))
      (node (ref "U6") (pin "14") (pinfunction "/RES_14") (pintype "input"))
    )
    (net (code "55") (name "RESET") (class "Default")
      (node (ref "K2") (pin "2") (pinfunction "2_2") (pintype "bidirectional"))
      (node (ref "U2") (pin "15") (pinfunction "RST_15") (pintype "bidirectional"))
    )
    (net (code "56") (name "SWCLK") (class "Default")
      (node (ref "J7") (pin "1") (pinfunction "1_1") (pintype "bidirectional"))
      (node (ref "U2") (pin "17") (pinfunction "PA30_SWCLK_17") (pintype "bidirectional"))
    )
    (net (code "57") (name "SWDIO") (class "Default")
      (node (ref "J7") (pin "2") (pinfunction "2_2") (pintype "bidirectional"))
      (node (ref "U2") (pin "18") (pinfunction "PA31_SWDIO_18") (pintype "bidirectional"))
    )
    (net (code "58") (name "SYS_3V3") (class "Default")
      (node (ref "BUZ1") (pin "+") (pinfunction "+_+") (pintype "bidirectional"))
      (node (ref "C10") (pin "1") (pinfunction "1_1") (pintype "passive"))
      (node (ref "C12") (pin "1") (pinfunction "1_1") (pintype "passive"))
      (node (ref "C20") (pin "2") (pinfunction "2_2") (pintype "passive"))
      (node (ref "C21") (pin "2") (pinfunction "2_2") (pintype "passive"))
      (node (ref "C24") (pin "2") (pinfunction "2_2") (pintype "passive"))
      (node (ref "C26") (pin "2") (pinfunction "2_2") (pintype "passive"))
      (node (ref "C29") (pin "2") (pinfunction "2_2") (pintype "passive"))
      (node (ref "D4") (pin "+") (pinfunction "+_+") (pintype "passive"))
      (node (ref "D5") (pin "-") (pinfunction "-_-") (pintype "passive"))
      (node (ref "FB1") (pin "1") (pinfunction "1_1") (pintype "bidirectional"))
      (node (ref "FB3") (pin "1") (pinfunction "1_1") (pintype "bidirectional"))
      (node (ref "J1") (pin "3") (pinfunction "3_3") (pintype "bidirectional"))
      (node (ref "J11") (pin "3") (pinfunction "3_3") (pintype "bidirectional"))
      (node (ref "J4") (pin "3") (pinfunction "3_3") (pintype "bidirectional"))
      (node (ref "J5") (pin "3") (pinfunction "3_3") (pintype "bidirectional"))
      (node (ref "J6") (pin "3") (pinfunction "3_3") (pintype "bidirectional"))
      (node (ref "J7") (pin "3") (pinfunction "3_3") (pintype "bidirectional"))
      (node (ref "L2") (pin "2") (pinfunction "2_2") (pintype "passive"))
      (node (ref "R10") (pin "2") (pinfunction "2_2") (pintype "passive"))
      (node (ref "R2") (pin "2") (pinfunction "2_2") (pintype "passive"))
      (node (ref "R40") (pin "2") (pinfunction "2_2") (pintype "passive"))
      (node (ref "R8") (pin "2") (pinfunction "2_2") (pintype "passive"))
      (node (ref "R9") (pin "2") (pinfunction "2_2") (pintype "passive"))
      (node (ref "U2") (pin "12") (pinfunction "3V3_12") (pintype "bidirectional"))
    )
    (net (code "59") (name "USB_5V") (class "Default")
      (node (ref "C22") (pin "1") (pinfunction "1_1") (pintype "passive"))
      (node (ref "C23") (pin "1") (pinfunction "1_1") (pintype "passive"))
      (node (ref "J11") (pin "1") (pinfunction "1_1") (pintype "bidirectional"))
      (node (ref "R16") (pin "1") (pinfunction "1_1") (pintype "passive"))
      (node (ref "U2") (pin "14") (pinfunction "5V_14") (pintype "bidirectional"))
      (node (ref "U5") (pin "2") (pinfunction "IN_2") (pintype "bidirectional"))
    )
    (net (code "60") (name "VBOOST_5V") (class "Default")
      (node (ref "C28") (pin "1") (pinfunction "1_1") (pintype "passive"))
      (node (ref "J7") (pin "6") (pinfunction "6_6") (pintype "bidirectional"))
      (node (ref "R5") (pin "1") (pinfunction "1_1") (pintype "passive"))
    )
    (net (code "61") (name "VDD_3V3_OLED") (class "Default")
      (node (ref "D2") (pin "-") (pinfunction "-_-") (pintype "passive"))
      (node (ref "FB1") (pin "2") (pinfunction "2_2") (pintype "bidirectional"))
      (node (ref "R21") (pin "2") (pinfunction "2_2") (pintype "passive"))
      (node (ref "R23") (pin "1") (pinfunction "1_1") (pintype "passive"))
      (node (ref "R25") (pin "1") (pinfunction "1_1") (pintype "passive"))
      (node (ref "U6") (pin "11") (pinfunction "BS1_11") (pintype "input"))
      (node (ref "U6") (pin "9") (pinfunction "VDD_9") (pintype "power_in"))
    )
    (net (code "62") (name "VDD_3V3_SD") (class "Default")
      (node (ref "C2") (pin "1") (pinfunction "1_1") (pintype "passive"))
      (node (ref "C3") (pin "1") (pinfunction "1_1") (pintype "passive"))
      (node (ref "D1") (pin "2") (pinfunction "2_2") (pintype "bidirectional"))
      (node (ref "FB3") (pin "2") (pinfunction "2_2") (pintype "bidirectional"))
      (node (ref "J3") (pin "4") (pinfunction "VDD_4") (pintype "bidirectional"))
      (node (ref "R60") (pin "2") (pinfunction "2_2") (pintype "passive"))
      (node (ref "R61") (pin "2") (pinfunction "2_2") (pintype "passive"))
      (node (ref "R62") (pin "2") (pinfunction "2_2") (pintype "passive"))
      (node (ref "R63") (pin "2") (pinfunction "2_2") (pintype "passive"))
      (node (ref "R64") (pin "2") (pinfunction "2_2") (pintype "passive"))
    )
    (net (code "63") (name "VSYS") (class "Default")
      (node (ref "C1") (pin "1") (pinfunction "1_1") (pintype "passive"))
      (node (ref "C11") (pin "1") (pinfunction "1_1") (pintype "passive"))
      (node (ref "C14") (pin "1") (pinfunction "1_1") (pintype "passive"))
      (node (ref "C15") (pin "2") (pinfunction "2_2") (pintype "passive"))
      (node (ref "C16") (pin "2") (pinfunction "2_2") (pintype "passive"))
      (node (ref "C18") (pin "1") (pinfunction "1_1") (pintype "passive"))
      (node (ref "C27") (pin "2") (pinfunction "2_2") (pintype "passive"))
      (node (ref "D16") (pin "+") (pinfunction "+_+") (pintype "passive"))
      (node (ref "L1") (pin "1") (pinfunction "1_1") (pintype "passive"))
      (node (ref "L3") (pin "2") (pinfunction "2_2") (pintype "passive"))
      (node (ref "U3") (pin "5") (pinfunction "EN_5") (pintype "bidirectional"))
      (node (ref "U3") (pin "7") (pinfunction "AVIN_7") (pintype "bidirectional"))
      (node (ref "U3") (pin "8") (pinfunction "PVIN_8") (pintype "bidirectional"))
      (node (ref "U4") (pin "3") (pinfunction "EN_3") (pintype "bidirectional"))
      (node (ref "U4") (pin "4") (pinfunction "IN_4") (pintype "bidirectional"))
      (node (ref "U5") (pin "1") (pinfunction "SYS_1") (pintype "bidirectional"))
      (node (ref "U5") (pin "15") (pinfunction "SYS_15") (pintype "bidirectional"))
    )
    (net (code "64") (name "unconnected-(J3-CDN-Pad9)") (class "Default")
      (node (ref "J3") (pin "9") (pinfunction "CDN_9") (pintype "bidirectional"))
    )
    (net (code "65") (name "unconnected-(J5-Pad2)") (class "Default")
      (node (ref "J5") (pin "2") (pinfunction "2_2") (pintype "bidirectional"))
    )
    (net (code "66") (name "unconnected-(JP2-R-Pad00)") (class "Default")
      (node (ref "JP2") (pin "00") (pinfunction "R_00") (pintype "bidirectional"))
    )
    (net (code "67") (name "unconnected-(SW1-PadCH1A)") (class "Default")
      (node (ref "SW1") (pin "CH1A") (pinfunction "CH1A_CH1A") (pintype "bidirectional"))
    )
    (net (code "68") (name "unconnected-(SW1-PadCH2A)") (class "Default")
      (node (ref "SW1") (pin "CH2A") (pinfunction "CH2A_CH2A") (pintype "bidirectional"))
    )
    (net (code "69") (name "unconnected-(U6-BS2-Pad12)") (class "Default")
      (node (ref "U6") (pin "12") (pinfunction "BS2_12") (pintype "input"))
    )
    (net (code "70") (name "unconnected-(U6-D3-Pad21)") (class "Default")
      (node (ref "U6") (pin "21") (pinfunction "D3_21") (pintype "input"))
    )
    (net (code "71") (name "unconnected-(U6-D4-Pad22)") (class "Default")
      (node (ref "U6") (pin "22") (pinfunction "D4_22") (pintype "input"))
    )
    (net (code "72") (name "unconnected-(U6-D5-Pad23)") (class "Default")
      (node (ref "U6") (pin "23") (pinfunction "D5_23") (pintype "input"))
    )
    (net (code "73") (name "unconnected-(U6-D6-Pad24)") (class "Default")
      (node (ref "U6") (pin "24") (pinfunction "D6_24") (pintype "input"))
    )
    (net (code "74") (name "unconnected-(U6-D7-Pad25)") (class "Default")
      (node (ref "U6") (pin "25") (pinfunction "D7_25") (pintype "input"))
    )
    (net (code "75") (name "unconnected-(U6-E{slash}RD-Pad17)") (class "Default")
      (node (ref "U6") (pin "17") (pinfunction "E/RD_17") (pintype "input"))
    )
    (net (code "76") (name "unconnected-(U6-NC-Pad7)") (class "Default")
      (node (ref "U6") (pin "7") (pinfunction "NC_7") (pintype "no_connect"))
    )
    (net (code "77") (name "unconnected-(U6-R{slash}W-Pad16)") (class "Default")
      (node (ref "U6") (pin "16") (pinfunction "R/W_16") (pintype "input"))
    )
  )
)
